# LimitSwitch.net
KiCad netlist of a schematic drawn in EAGLE
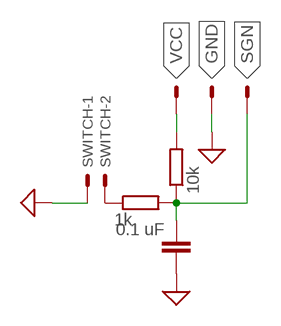
[diagram p0: schematic, sheet 1]

(export (version "E")
  (design (tool "Eeschema 10.0.6"))
  (components
    (comp (ref "C1")
      (value "0.1 uF")
      (footprint "eagle-import:C1206")
      (libsource (lib "eagle-import") (part "C-EUC1206"))
    )
    (comp (ref "INPUT")
      (value "22-23-2031")
      (footprint "eagle-import:22-23-2031")
      (fields (field (name "MF") "MOLEX"))
      (libsource (lib "eagle-import") (part "22-23-2031"))
    )
    (comp (ref "R3")
      (value "10k")
      (footprint "eagle-import:R1206")
      (libsource (lib "eagle-import") (part "R-EU_R1206"))
    )
    (comp (ref "R4")
      (value "1k")
      (footprint "eagle-import:R1206")
      (libsource (lib "eagle-import") (part "R-EU_R1206"))
    )
    (comp (ref "SWITCH")
      (value "22-23-2021")
      (footprint "eagle-import:22-23-2021")
      (fields (field (name "MF") "MOLEX"))
      (libsource (lib "eagle-import") (part "22-23-2021"))
    )
  )
  (nets
    (net (code "1") (name "GND") (class "Default")
      (node (ref "C1") (pin "2") (pinfunction "2_2") (pintype "passive"))
      (node (ref "INPUT") (pin "2") (pinfunction "S_2") (pintype "passive"))
      (node (ref "SWITCH") (pin "1") (pinfunction "S_1") (pintype "passive"))
    )
    (net (code "2") (name "Net-(SWITCHB-S)") (class "Default")
      (node (ref "R4") (pin "1") (pinfunction "1_1") (pintype "passive"))
      (node (ref "SWITCH") (pin "2") (pinfunction "S_2") (pintype "passive"))
    )
    (net (code "3") (name "SGN") (class "Default")
      (node (ref "C1") (pin "1") (pinfunction "1_1") (pintype "passive"))
      (node (ref "INPUT") (pin "3") (pinfunction "S_3") (pintype "passive"))
      (node (ref "R3") (pin "1") (pinfunction "1_1") (pintype "passive"))
      (node (ref "R4") (pin "2") (pinfunction "2_2") (pintype "passive"))
    )
    (net (code "4") (name "VCC") (class "Default")
      (node (ref "INPUT") (pin "1") (pinfunction "S_1") (pintype "passive"))
      (node (ref "R3") (pin "2") (pinfunction "2_2") (pintype "passive"))
    )
  )
)
